# Motor_Control.net
KiCad netlist of a schematic drawn in Altium Designer
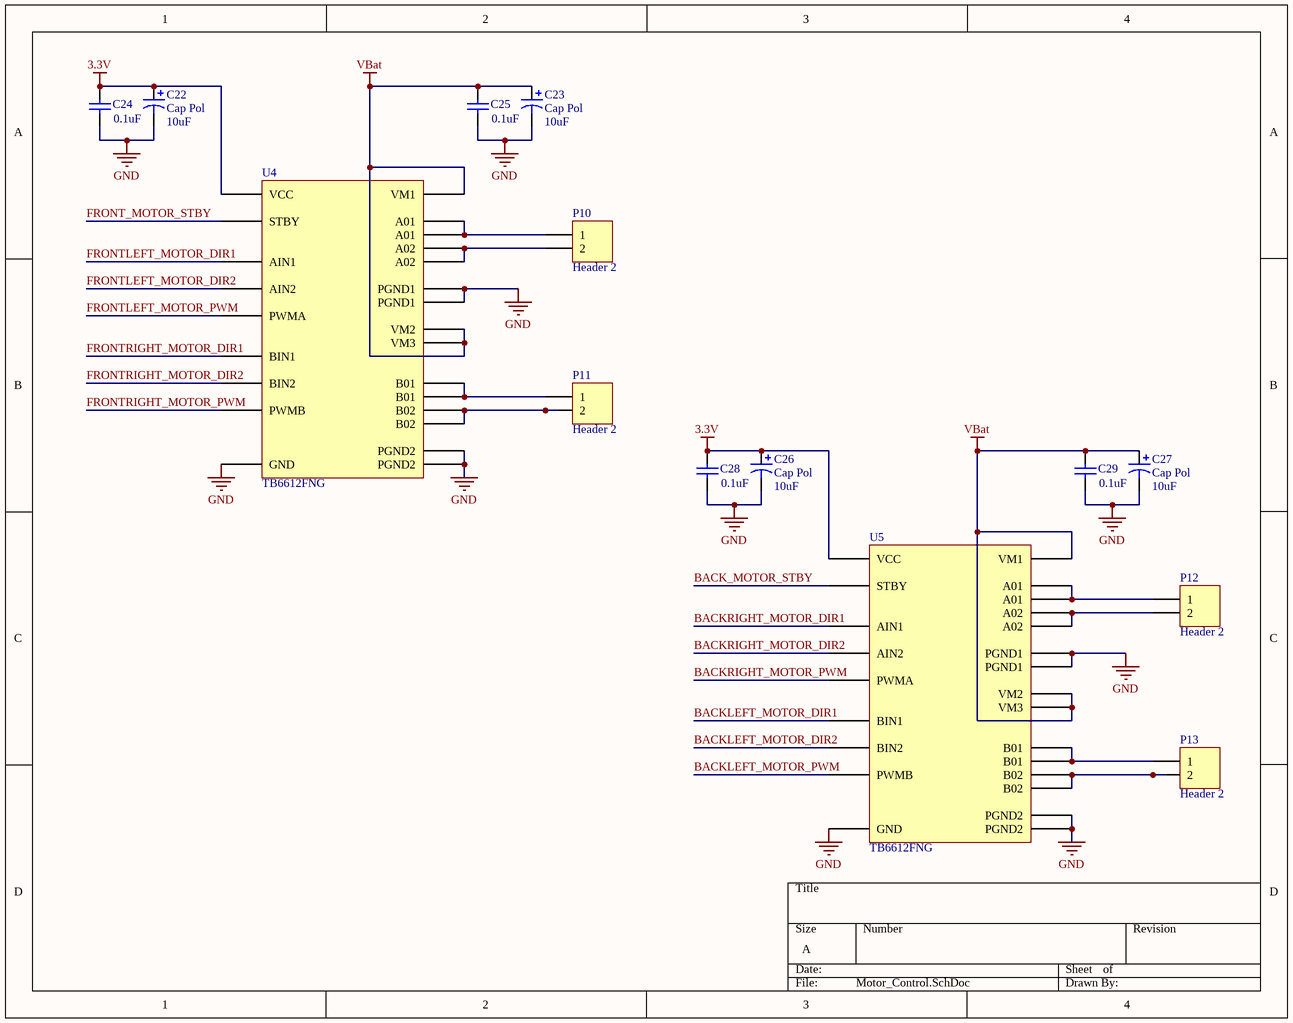
[diagram p0: Motor_Control.SchDoc]

(export (version "E")
  (design (tool "Eeschema 10.0.6"))
  (components
    (comp (ref "C22")
      (value "Cap Pol")
      (footprint "1206")
      (description "Polarized Capacitor")
      (fields (field (name "ALTIUM_VALUE") "10uF"))
      (libsource (lib "passives") (part "Cap Pol"))
    )
    (comp (ref "C23")
      (value "Cap Pol")
      (footprint "1206")
      (description "Polarized Capacitor")
      (fields (field (name "ALTIUM_VALUE") "10uF"))
      (libsource (lib "passives") (part "Cap Pol"))
    )
    (comp (ref "C24")
      (value "0.1uF")
      (footprint "0805")
      (description "Capacitor")
      (fields (field (name "Comment") "Cap"))
      (libsource (lib "passives") (part "Cap"))
    )
    (comp (ref "C25")
      (value "0.1uF")
      (footprint "0805")
      (description "Capacitor")
      (fields (field (name "Comment") "Cap"))
      (libsource (lib "passives") (part "Cap"))
    )
    (comp (ref "C26")
      (value "Cap Pol")
      (footprint "1206")
      (description "Polarized Capacitor")
      (fields (field (name "ALTIUM_VALUE") "10uF"))
      (libsource (lib "passives") (part "Cap Pol"))
    )
    (comp (ref "C27")
      (value "Cap Pol")
      (footprint "1206")
      (description "Polarized Capacitor")
      (fields (field (name "ALTIUM_VALUE") "10uF"))
      (libsource (lib "passives") (part "Cap Pol"))
    )
    (comp (ref "C28")
      (value "0.1uF")
      (footprint "0805")
      (description "Capacitor")
      (fields (field (name "Comment") "Cap"))
      (libsource (lib "passives") (part "Cap"))
    )
    (comp (ref "C29")
      (value "0.1uF")
      (footprint "0805")
      (description "Capacitor")
      (fields (field (name "Comment") "Cap"))
      (libsource (lib "passives") (part "Cap"))
    )
    (comp (ref "P10")
      (value "Header 2")
      (footprint "HDR1X2")
      (description "Header, 2-Pin")
      (fields (field (name "PUBLISHER") "Altium Limited"))
      (libsource (lib "Miscellaneous Connectors") (part "Header 2"))
    )
    (comp (ref "P11")
      (value "Header 2")
      (footprint "HDR1X2")
      (description "Header, 2-Pin")
      (fields (field (name "PUBLISHER") "Altium Limited"))
      (libsource (lib "Miscellaneous Connectors") (part "Header 2"))
    )
    (comp (ref "P12")
      (value "Header 2")
      (footprint "HDR1X2")
      (description "Header, 2-Pin")
      (fields (field (name "PUBLISHER") "Altium Limited"))
      (libsource (lib "Miscellaneous Connectors") (part "Header 2"))
    )
    (comp (ref "P13")
      (value "Header 2")
      (footprint "HDR1X2")
      (description "Header, 2-Pin")
      (fields (field (name "PUBLISHER") "Altium Limited"))
      (libsource (lib "Miscellaneous Connectors") (part "Header 2"))
    )
    (comp (ref "U4")
      (value "TB6612FNG")
      (footprint "SSOP24-P-300-0.65A")
      (fields
        (field (name "VENDOR PART NO.") "TB6612FNG(OC8EL)CT-ND")
        (field (name "MANUFACTURER") "Toshiba")
      )
      (libsource (lib "Devices") (part "TB6612FNG"))
    )
    (comp (ref "U5")
      (value "TB6612FNG")
      (footprint "SSOP24-P-300-0.65A")
      (fields
        (field (name "VENDOR PART NO.") "TB6612FNG(OC8EL)CT-ND")
        (field (name "MANUFACTURER") "Toshiba")
      )
      (libsource (lib "Devices") (part "TB6612FNG"))
    )
  )
  (nets
    (net (code "1") (name "/BACKLEFT_MOTOR_DIR1") (class "Default")
      (node (ref "U5") (pin "17") (pinfunction "BIN1_17") (pintype "passive"))
    )
    (net (code "2") (name "/BACKLEFT_MOTOR_DIR2") (class "Default")
      (node (ref "U5") (pin "16") (pinfunction "BIN2_16") (pintype "passive"))
    )
    (net (code "3") (name "/BACKLEFT_MOTOR_PWM") (class "Default")
      (node (ref "U5") (pin "15") (pinfunction "PWMB_15") (pintype "passive"))
    )
    (net (code "4") (name "/BACKRIGHT_MOTOR_DIR1") (class "Default")
      (node (ref "U5") (pin "21") (pinfunction "AIN1_21") (pintype "passive"))
    )
    (net (code "5") (name "/BACKRIGHT_MOTOR_DIR2") (class "Default")
      (node (ref "U5") (pin "22") (pinfunction "AIN2_22") (pintype "passive"))
    )
    (net (code "6") (name "/BACKRIGHT_MOTOR_PWM") (class "Default")
      (node (ref "U5") (pin "23") (pinfunction "PWMA_23") (pintype "passive"))
    )
    (net (code "7") (name "/BACK_MOTOR_STBY") (class "Default")
      (node (ref "U5") (pin "19") (pinfunction "STBY_19") (pintype "passive"))
    )
    (net (code "8") (name "/FRONTLEFT_MOTOR_DIR1") (class "Default")
      (node (ref "U4") (pin "21") (pinfunction "AIN1_21") (pintype "passive"))
    )
    (net (code "9") (name "/FRONTLEFT_MOTOR_DIR2") (class "Default")
      (node (ref "U4") (pin "22") (pinfunction "AIN2_22") (pintype "passive"))
    )
    (net (code "10") (name "/FRONTLEFT_MOTOR_PWM") (class "Default")
      (node (ref "U4") (pin "23") (pinfunction "PWMA_23") (pintype "passive"))
    )
    (net (code "11") (name "/FRONTRIGHT_MOTOR_DIR1") (class "Default")
      (node (ref "U4") (pin "17") (pinfunction "BIN1_17") (pintype "passive"))
    )
    (net (code "12") (name "/FRONTRIGHT_MOTOR_DIR2") (class "Default")
      (node (ref "U4") (pin "16") (pinfunction "BIN2_16") (pintype "passive"))
    )
    (net (code "13") (name "/FRONTRIGHT_MOTOR_PWM") (class "Default")
      (node (ref "U4") (pin "15") (pinfunction "PWMB_15") (pintype "passive"))
    )
    (net (code "14") (name "/FRONT_MOTOR_STBY") (class "Default")
      (node (ref "U4") (pin "19") (pinfunction "STBY_19") (pintype "passive"))
    )
    (net (code "15") (name "3.3V") (class "Default")
      (node (ref "C22") (pin "1") (pinfunction "1_1") (pintype "passive"))
      (node (ref "C24") (pin "2") (pinfunction "2_2") (pintype "passive"))
      (node (ref "C26") (pin "1") (pinfunction "1_1") (pintype "passive"))
      (node (ref "C28") (pin "2") (pinfunction "2_2") (pintype "passive"))
      (node (ref "U4") (pin "20") (pinfunction "VCC_20") (pintype "passive"))
      (node (ref "U5") (pin "20") (pinfunction "VCC_20") (pintype "passive"))
    )
    (net (code "16") (name "GND") (class "Default")
      (node (ref "C22") (pin "2") (pinfunction "2_2") (pintype "passive"))
      (node (ref "C23") (pin "2") (pinfunction "2_2") (pintype "passive"))
      (node (ref "C24") (pin "1") (pinfunction "1_1") (pintype "passive"))
      (node (ref "C25") (pin "1") (pinfunction "1_1") (pintype "passive"))
      (node (ref "C26") (pin "2") (pinfunction "2_2") (pintype "passive"))
      (node (ref "C27") (pin "2") (pinfunction "2_2") (pintype "passive"))
      (node (ref "C28") (pin "1") (pinfunction "1_1") (pintype "passive"))
      (node (ref "C29") (pin "1") (pinfunction "1_1") (pintype "passive"))
      (node (ref "U4") (pin "10") (pinfunction "PGND2_10") (pintype "passive"))
      (node (ref "U4") (pin "18") (pinfunction "GND_18") (pintype "passive"))
      (node (ref "U4") (pin "3") (pinfunction "PGND1_3") (pintype "passive"))
      (node (ref "U4") (pin "4") (pinfunction "PGND1_4") (pintype "passive"))
      (node (ref "U4") (pin "9") (pinfunction "PGND2_9") (pintype "passive"))
      (node (ref "U5") (pin "10") (pinfunction "PGND2_10") (pintype "passive"))
      (node (ref "U5") (pin "18") (pinfunction "GND_18") (pintype "passive"))
      (node (ref "U5") (pin "3") (pinfunction "PGND1_3") (pintype "passive"))
      (node (ref "U5") (pin "4") (pinfunction "PGND1_4") (pintype "passive"))
      (node (ref "U5") (pin "9") (pinfunction "PGND2_9") (pintype "passive"))
    )
    (net (code "17") (name "Net-(P10-Pad1)") (class "Default")
      (node (ref "P10") (pin "1") (pinfunction "1_1") (pintype "passive"))
      (node (ref "U4") (pin "1") (pinfunction "A01_1") (pintype "passive"))
      (node (ref "U4") (pin "2") (pinfunction "A01_2") (pintype "passive"))
    )
    (net (code "18") (name "Net-(P10-Pad2)") (class "Default")
      (node (ref "P10") (pin "2") (pinfunction "2_2") (pintype "passive"))
      (node (ref "U4") (pin "5") (pinfunction "A02_5") (pintype "passive"))
      (node (ref "U4") (pin "6") (pinfunction "A02_6") (pintype "passive"))
    )
    (net (code "19") (name "Net-(P11-Pad1)") (class "Default")
      (node (ref "P11") (pin "1") (pinfunction "1_1") (pintype "passive"))
      (node (ref "U4") (pin "11") (pinfunction "B01_11") (pintype "passive"))
      (node (ref "U4") (pin "12") (pinfunction "B01_12") (pintype "passive"))
    )
    (net (code "20") (name "Net-(P11-Pad2)") (class "Default")
      (node (ref "P11") (pin "2") (pinfunction "2_2") (pintype "passive"))
      (node (ref "U4") (pin "7") (pinfunction "B02_7") (pintype "passive"))
      (node (ref "U4") (pin "8") (pinfunction "B02_8") (pintype "passive"))
    )
    (net (code "21") (name "Net-(P12-Pad1)") (class "Default")
      (node (ref "P12") (pin "1") (pinfunction "1_1") (pintype "passive"))
      (node (ref "U5") (pin "1") (pinfunction "A01_1") (pintype "passive"))
      (node (ref "U5") (pin "2") (pinfunction "A01_2") (pintype "passive"))
    )
    (net (code "22") (name "Net-(P12-Pad2)") (class "Default")
      (node (ref "P12") (pin "2") (pinfunction "2_2") (pintype "passive"))
      (node (ref "U5") (pin "5") (pinfunction "A02_5") (pintype "passive"))
      (node (ref "U5") (pin "6") (pinfunction "A02_6") (pintype "passive"))
    )
    (net (code "23") (name "Net-(P13-Pad1)") (class "Default")
      (node (ref "P13") (pin "1") (pinfunction "1_1") (pintype "passive"))
      (node (ref "U5") (pin "11") (pinfunction "B01_11") (pintype "passive"))
      (node (ref "U5") (pin "12") (pinfunction "B01_12") (pintype "passive"))
    )
    (net (code "24") (name "Net-(P13-Pad2)") (class "Default")
      (node (ref "P13") (pin "2") (pinfunction "2_2") (pintype "passive"))
      (node (ref "U5") (pin "7") (pinfunction "B02_7") (pintype "passive"))
      (node (ref "U5") (pin "8") (pinfunction "B02_8") (pintype "passive"))
    )
    (net (code "25") (name "VBat") (class "Default")
      (node (ref "C23") (pin "1") (pinfunction "1_1") (pintype "passive"))
      (node (ref "C25") (pin "2") (pinfunction "2_2") (pintype "passive"))
      (node (ref "C27") (pin "1") (pinfunction "1_1") (pintype "passive"))
      (node (ref "C29") (pin "2") (pinfunction "2_2") (pintype "passive"))
      (node (ref "U4") (pin "13") (pinfunction "VM2_13") (pintype "passive"))
      (node (ref "U4") (pin "14") (pinfunction "VM3_14") (pintype "passive"))
      (node (ref "U4") (pin "24") (pinfunction "VM1_24") (pintype "passive"))
      (node (ref "U5") (pin "13") (pinfunction "VM2_13") (pintype "passive"))
      (node (ref "U5") (pin "14") (pinfunction "VM3_14") (pintype "passive"))
      (node (ref "U5") (pin "24") (pinfunction "VM1_24") (pintype "passive"))
    )
  )
)
